# mapleSDuino-Large-V0_1_005.net
KiCad netlist of a schematic drawn in EAGLE
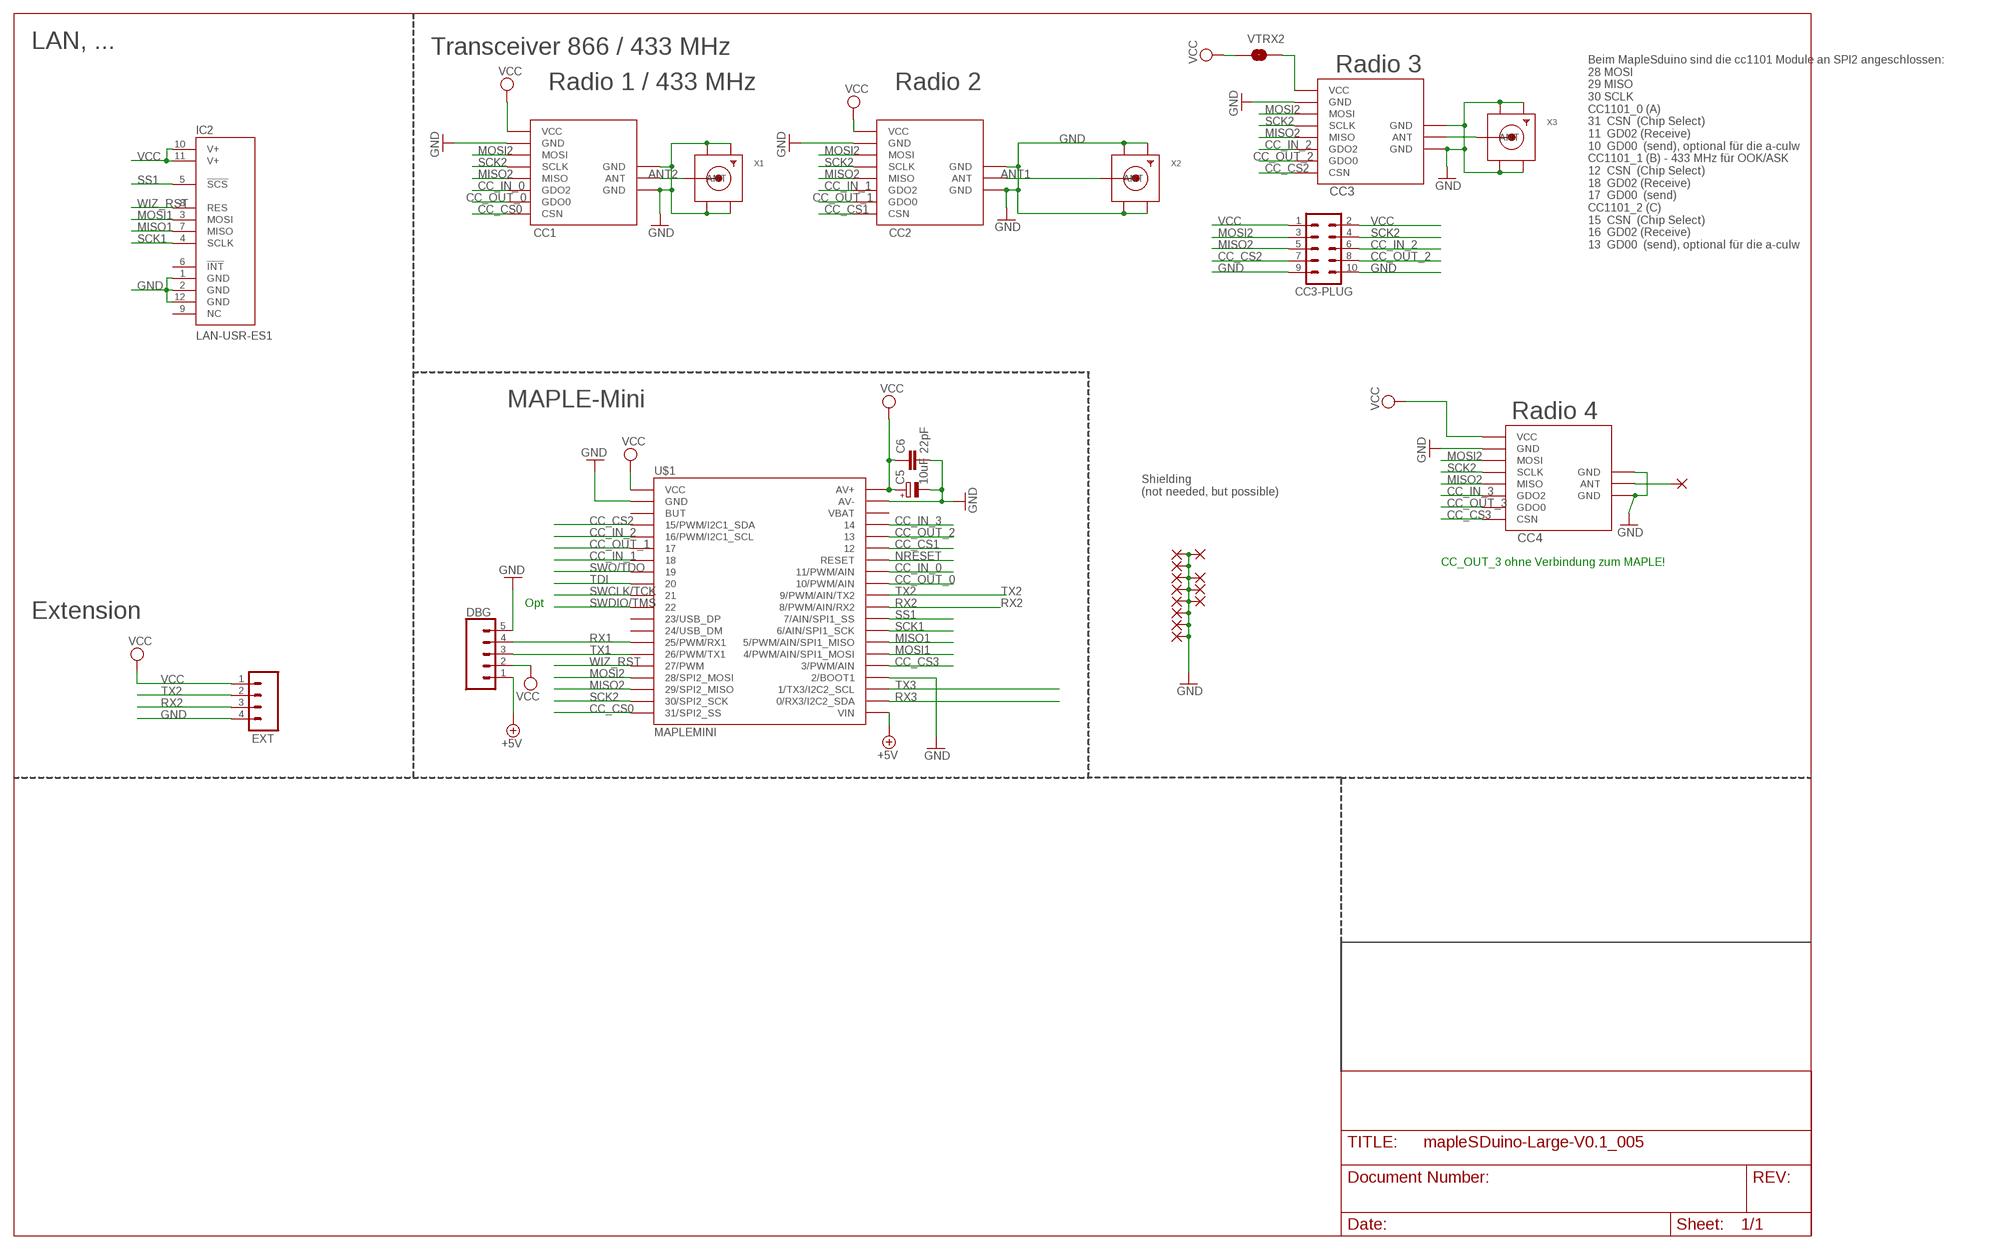
[diagram p0: schematic, sheet 1]

(export (version "E")
  (design (tool "Eeschema 10.0.6"))
  (components
    (comp (ref "C5")
      (value "10uF")
      (footprint "eagle-import:R_2012-12W")
      (libsource (lib "eagle-import") (part "CPOL-EUR/2012-12W"))
    )
    (comp (ref "C6")
      (value "22pF")
      (footprint "eagle-import:C0805")
      (libsource (lib "eagle-import") (part "C-EUC0805"))
    )
    (comp (ref "CC1")
      (value "CC1101")
      (footprint "eagle-import:CC1101_MODULE1_SMD")
      (libsource (lib "eagle-import") (part "CC1101_MODULE1SMD"))
    )
    (comp (ref "CC2")
      (value "CC1101_MODULE1SMD")
      (footprint "eagle-import:CC1101_MODULE1_SMD")
      (libsource (lib "eagle-import") (part "CC1101_MODULE1SMD"))
    )
    (comp (ref "CC3")
      (value "CC1101_MODULE1SMD")
      (footprint "eagle-import:CC1101_MODULE1_SMD")
      (libsource (lib "eagle-import") (part "wireless_CC1101_MODULE1SMD"))
    )
    (comp (ref "CC3-PLUG")
      (value "MA05-2")
      (footprint "eagle-import:MA05-2")
      (libsource (lib "eagle-import") (part "MA05-2"))
    )
    (comp (ref "CC4")
      (value "CC1101_MODULE1SMD")
      (footprint "eagle-import:CC1101_MODULE1_SMD")
      (libsource (lib "eagle-import") (part "wireless_CC1101_MODULE1SMD"))
    )
    (comp (ref "DBG")
      (value "CONN_05LOCK")
      (footprint "eagle-import:1X05_LOCK")
      (libsource (lib "eagle-import") (part "CONN_05LOCK"))
    )
    (comp (ref "EXT")
      (value "CONN_04PTH")
      (footprint "eagle-import:1X04")
      (libsource (lib "eagle-import") (part "CONN_04PTH"))
    )
    (comp (ref "IC2")
      (value "LAN-USR-ES1")
      (footprint "eagle-import:USR-ES1")
      (libsource (lib "eagle-import") (part "LAN-USR-ES1"))
    )
    (comp (ref "PAD1")
      (value "WIREPADSMD1,27-254")
      (footprint "eagle-import:SMD1,27-2,54")
      (libsource (lib "eagle-import") (part "WIREPADSMD1,27-254"))
    )
    (comp (ref "PAD2")
      (value "WIREPADSMD1,27-254")
      (footprint "eagle-import:SMD1,27-2,54")
      (libsource (lib "eagle-import") (part "WIREPADSMD1,27-254"))
    )
    (comp (ref "PAD3")
      (value "WIREPADSMD1,27-254")
      (footprint "eagle-import:SMD1,27-2,54")
      (libsource (lib "eagle-import") (part "WIREPADSMD1,27-254"))
    )
    (comp (ref "PAD4")
      (value "WIREPADSMD1,27-254")
      (footprint "eagle-import:SMD1,27-2,54")
      (libsource (lib "eagle-import") (part "WIREPADSMD1,27-254"))
    )
    (comp (ref "PAD5")
      (value "WIREPADSMD1,27-254")
      (footprint "eagle-import:SMD1,27-2,54")
      (libsource (lib "eagle-import") (part "WIREPADSMD1,27-254"))
    )
    (comp (ref "PAD6")
      (value "WIREPADSMD1,27-254")
      (footprint "eagle-import:SMD1,27-2,54")
      (libsource (lib "eagle-import") (part "WIREPADSMD1,27-254"))
    )
    (comp (ref "PAD7")
      (value "WIREPADSMD1,27-254")
      (footprint "eagle-import:SMD1,27-2,54")
      (libsource (lib "eagle-import") (part "WIREPADSMD1,27-254"))
    )
    (comp (ref "PAD8")
      (value "WIREPADSMD1,27-254")
      (footprint "eagle-import:SMD1,27-2,54")
      (libsource (lib "eagle-import") (part "WIREPADSMD1,27-254"))
    )
    (comp (ref "PAD9")
      (value "WIREPADSMD1,27-254")
      (footprint "eagle-import:SMD1,27-2,54")
      (libsource (lib "eagle-import") (part "WIREPADSMD1,27-254"))
    )
    (comp (ref "PAD10")
      (value "WIREPADSMD1,27-254")
      (footprint "eagle-import:SMD1,27-2,54")
      (libsource (lib "eagle-import") (part "WIREPADSMD1,27-254"))
    )
    (comp (ref "PAD11")
      (value "WIREPADSMD1,27-254")
      (footprint "eagle-import:SMD1,27-2,54")
      (libsource (lib "eagle-import") (part "WIREPADSMD1,27-254"))
    )
    (comp (ref "PAD12")
      (value "WIREPADSMD1,27-254")
      (footprint "eagle-import:SMD1,27-2,54")
      (libsource (lib "eagle-import") (part "WIREPADSMD1,27-254"))
    )
    (comp (ref "PAD13")
      (value "WIREPADSMD1,27-254")
      (footprint "eagle-import:SMD1,27-2,54")
      (libsource (lib "eagle-import") (part "WIREPADSMD1,27-254"))
    )
    (comp (ref "U$1")
      (value "MAPLEMINI")
      (footprint "eagle-import:20-DIP")
      (libsource (lib "eagle-import") (part "MAPLEMINI"))
    )
    (comp (ref "VTRX2")
      (value "JUMPER-SMT_2_NC_TRACE_SILK")
      (footprint "eagle-import:SMT-JUMPER_2_NC_TRACE_SILK")
      (libsource (lib "eagle-import") (part "JUMPER-SMT_2_NC_TRACE_SILK"))
    )
    (comp (ref "X1")
      (value "SMACONNECTOR_EDGE")
      (footprint "eagle-import:SMA_EDGELAUNCH")
      (libsource (lib "eagle-import") (part "SMACONNECTOR_EDGE"))
    )
    (comp (ref "X2")
      (value "SMACONNECTOR_EDGE")
      (footprint "eagle-import:SMA_EDGELAUNCH")
      (libsource (lib "eagle-import") (part "SMACONNECTOR_EDGE"))
    )
    (comp (ref "X3")
      (value "SMACONNECTOR_EDGE")
      (footprint "eagle-import:SMA_EDGELAUNCH")
      (libsource (lib "eagle-import") (part "SMACONNECTOR_EDGE"))
    )
  )
  (nets
    (net (code "1") (name "+5V") (class "Default")
      (node (ref "DBG") (pin "1") (pinfunction "1_1") (pintype "passive"))
      (node (ref "U$1") (pin "21") (pinfunction "VIN_21") (pintype "bidirectional"))
    )
    (net (code "2") (name "/ANT1") (class "Default")
      (node (ref "CC2") (pin "ANT") (pinfunction "ANT_ANT") (pintype "output"))
      (node (ref "X2") (pin "P") (pinfunction "ANT_P") (pintype "bidirectional"))
    )
    (net (code "3") (name "/ANT2") (class "Default")
      (node (ref "CC1") (pin "ANT") (pinfunction "ANT_ANT") (pintype "output"))
      (node (ref "X1") (pin "P") (pinfunction "ANT_P") (pintype "bidirectional"))
    )
    (net (code "4") (name "/CC_CS0") (class "Default")
      (node (ref "CC1") (pin "CSN") (pinfunction "CSN_CSN") (pintype "bidirectional"))
      (node (ref "U$1") (pin "20") (pinfunction "31/SPI2_SS_20") (pintype "bidirectional"))
    )
    (net (code "5") (name "/CC_CS1") (class "Default")
      (node (ref "CC2") (pin "CSN") (pinfunction "CSN_CSN") (pintype "bidirectional"))
      (node (ref "U$1") (pin "35") (pinfunction "12_35") (pintype "bidirectional"))
    )
    (net (code "6") (name "/CC_CS2") (class "Default")
      (node (ref "CC3") (pin "CSN") (pinfunction "CSN_CSN") (pintype "bidirectional"))
      (node (ref "CC3-PLUG") (pin "7") (pinfunction "7_7") (pintype "passive"))
      (node (ref "U$1") (pin "4") (pinfunction "15/PWM/I2C1_SDA_4") (pintype "bidirectional"))
    )
    (net (code "7") (name "/CC_CS3") (class "Default")
      (node (ref "CC4") (pin "CSN") (pinfunction "CSN_CSN") (pintype "bidirectional"))
      (node (ref "U$1") (pin "25") (pinfunction "3/PWM/AIN_25") (pintype "bidirectional"))
    )
    (net (code "8") (name "/CC_IN_0") (class "Default")
      (node (ref "CC1") (pin "GDO2") (pinfunction "GDO2_GDO2") (pintype "bidirectional"))
      (node (ref "U$1") (pin "33") (pinfunction "11/PWM/AIN_33") (pintype "bidirectional"))
    )
    (net (code "9") (name "/CC_IN_1") (class "Default")
      (node (ref "CC2") (pin "GDO2") (pinfunction "GDO2_GDO2") (pintype "bidirectional"))
      (node (ref "U$1") (pin "7") (pinfunction "18_7") (pintype "bidirectional"))
    )
    (net (code "10") (name "/CC_IN_2") (class "Default")
      (node (ref "CC3") (pin "GDO2") (pinfunction "GDO2_GDO2") (pintype "bidirectional"))
      (node (ref "CC3-PLUG") (pin "6") (pinfunction "6_6") (pintype "passive"))
      (node (ref "U$1") (pin "5") (pinfunction "16/PWM/I2C1_SCL_5") (pintype "bidirectional"))
    )
    (net (code "11") (name "/CC_IN_3") (class "Default")
      (node (ref "CC4") (pin "GDO2") (pinfunction "GDO2_GDO2") (pintype "bidirectional"))
      (node (ref "U$1") (pin "37") (pinfunction "14_37") (pintype "bidirectional"))
    )
    (net (code "12") (name "/CC_OUT_0") (class "Default")
      (node (ref "CC1") (pin "GDO0") (pinfunction "GDO0_GDO0") (pintype "bidirectional"))
      (node (ref "U$1") (pin "32") (pinfunction "10/PWM/AIN_32") (pintype "bidirectional"))
    )
    (net (code "13") (name "/CC_OUT_1") (class "Default")
      (node (ref "CC2") (pin "GDO0") (pinfunction "GDO0_GDO0") (pintype "bidirectional"))
      (node (ref "U$1") (pin "6") (pinfunction "17_6") (pintype "bidirectional"))
    )
    (net (code "14") (name "/CC_OUT_2") (class "Default")
      (node (ref "CC3") (pin "GDO0") (pinfunction "GDO0_GDO0") (pintype "bidirectional"))
      (node (ref "CC3-PLUG") (pin "8") (pinfunction "8_8") (pintype "passive"))
      (node (ref "U$1") (pin "36") (pinfunction "13_36") (pintype "bidirectional"))
    )
    (net (code "15") (name "/CC_OUT_3") (class "Default")
      (node (ref "CC4") (pin "GDO0") (pinfunction "GDO0_GDO0") (pintype "bidirectional"))
    )
    (net (code "16") (name "/MISO1") (class "Default")
      (node (ref "IC2") (pin "7") (pinfunction "MISO_7") (pintype "bidirectional"))
      (node (ref "U$1") (pin "27") (pinfunction "5/PWM/AIN/SPI1_MISO_27") (pintype "bidirectional"))
    )
    (net (code "17") (name "/MISO2") (class "Default")
      (node (ref "CC1") (pin "MISO") (pinfunction "MISO_MISO") (pintype "bidirectional"))
      (node (ref "CC2") (pin "MISO") (pinfunction "MISO_MISO") (pintype "bidirectional"))
      (node (ref "CC3") (pin "MISO") (pinfunction "MISO_MISO") (pintype "bidirectional"))
      (node (ref "CC3-PLUG") (pin "5") (pinfunction "5_5") (pintype "passive"))
      (node (ref "CC4") (pin "MISO") (pinfunction "MISO_MISO") (pintype "bidirectional"))
      (node (ref "U$1") (pin "18") (pinfunction "29/SPI2_MISO_18") (pintype "bidirectional"))
    )
    (net (code "18") (name "/MOSI1") (class "Default")
      (node (ref "IC2") (pin "3") (pinfunction "MOSI_3") (pintype "bidirectional"))
      (node (ref "U$1") (pin "26") (pinfunction "4/PWM/AIN/SPI1_MOSI_26") (pintype "bidirectional"))
    )
    (net (code "19") (name "/MOSI2") (class "Default")
      (node (ref "CC1") (pin "MOSI") (pinfunction "MOSI_MOSI") (pintype "bidirectional"))
      (node (ref "CC2") (pin "MOSI") (pinfunction "MOSI_MOSI") (pintype "bidirectional"))
      (node (ref "CC3") (pin "MOSI") (pinfunction "MOSI_MOSI") (pintype "bidirectional"))
      (node (ref "CC3-PLUG") (pin "3") (pinfunction "3_3") (pintype "passive"))
      (node (ref "CC4") (pin "MOSI") (pinfunction "MOSI_MOSI") (pintype "bidirectional"))
      (node (ref "U$1") (pin "17") (pinfunction "28/SPI2_MOSI_17") (pintype "bidirectional"))
    )
    (net (code "20") (name "/NRESET") (class "Default")
      (node (ref "U$1") (pin "34") (pinfunction "RESET_34") (pintype "bidirectional"))
    )
    (net (code "21") (name "/RX1") (class "Default")
      (node (ref "DBG") (pin "4") (pinfunction "4_4") (pintype "passive"))
      (node (ref "U$1") (pin "14") (pinfunction "25/PWM/RX1_14") (pintype "bidirectional"))
    )
    (net (code "22") (name "/RX2") (class "Default")
      (node (ref "EXT") (pin "3") (pinfunction "3_3") (pintype "passive"))
      (node (ref "U$1") (pin "30") (pinfunction "8/PWM/AIN/RX2_30") (pintype "bidirectional"))
    )
    (net (code "23") (name "/RX3") (class "Default")
      (node (ref "U$1") (pin "22") (pinfunction "0/RX3/I2C2_SDA_22") (pintype "bidirectional"))
    )
    (net (code "24") (name "/SCK1") (class "Default")
      (node (ref "IC2") (pin "4") (pinfunction "SCLK_4") (pintype "input"))
      (node (ref "U$1") (pin "28") (pinfunction "6/AIN/SPI1_SCK_28") (pintype "bidirectional"))
    )
    (net (code "25") (name "/SCK2") (class "Default")
      (node (ref "CC1") (pin "SCLK") (pinfunction "SCLK_SCLK") (pintype "bidirectional"))
      (node (ref "CC2") (pin "SCLK") (pinfunction "SCLK_SCLK") (pintype "bidirectional"))
      (node (ref "CC3") (pin "SCLK") (pinfunction "SCLK_SCLK") (pintype "bidirectional"))
      (node (ref "CC3-PLUG") (pin "4") (pinfunction "4_4") (pintype "passive"))
      (node (ref "CC4") (pin "SCLK") (pinfunction "SCLK_SCLK") (pintype "bidirectional"))
      (node (ref "U$1") (pin "19") (pinfunction "30/SPI2_SCK_19") (pintype "bidirectional"))
    )
    (net (code "26") (name "/SS1") (class "Default")
      (node (ref "IC2") (pin "5") (pinfunction "~{SCS}_5") (pintype "input"))
      (node (ref "U$1") (pin "29") (pinfunction "7/AIN/SPI1_SS_29") (pintype "bidirectional"))
    )
    (net (code "27") (name "/SWCLK{slash}TCK") (class "Default")
      (node (ref "U$1") (pin "10") (pinfunction "21_10") (pintype "bidirectional"))
    )
    (net (code "28") (name "/SWDIO{slash}TMS") (class "Default")
      (node (ref "U$1") (pin "11") (pinfunction "22_11") (pintype "bidirectional"))
    )
    (net (code "29") (name "/SWO{slash}TDO") (class "Default")
      (node (ref "U$1") (pin "8") (pinfunction "19_8") (pintype "bidirectional"))
    )
    (net (code "30") (name "/TDI") (class "Default")
      (node (ref "U$1") (pin "9") (pinfunction "20_9") (pintype "bidirectional"))
    )
    (net (code "31") (name "/TX1") (class "Default")
      (node (ref "DBG") (pin "3") (pinfunction "3_3") (pintype "passive"))
      (node (ref "U$1") (pin "15") (pinfunction "26/PWM/TX1_15") (pintype "bidirectional"))
    )
    (net (code "32") (name "/TX2") (class "Default")
      (node (ref "EXT") (pin "2") (pinfunction "2_2") (pintype "passive"))
      (node (ref "U$1") (pin "31") (pinfunction "9/PWM/AIN/TX2_31") (pintype "bidirectional"))
    )
    (net (code "33") (name "/TX3") (class "Default")
      (node (ref "U$1") (pin "23") (pinfunction "1/TX3/I2C2_SCL_23") (pintype "bidirectional"))
    )
    (net (code "34") (name "/WIZ_RST") (class "Default")
      (node (ref "IC2") (pin "8") (pinfunction "RES_8") (pintype "input"))
      (node (ref "U$1") (pin "16") (pinfunction "27/PWM_16") (pintype "bidirectional"))
    )
    (net (code "35") (name "GND") (class "Default")
      (node (ref "C5") (pin "-") (pinfunction "-_-") (pintype "passive"))
      (node (ref "C6") (pin "2") (pinfunction "2_2") (pintype "passive"))
      (node (ref "CC1") (pin "GND@0") (pinfunction "GND_GND@0") (pintype "power_in"))
      (node (ref "CC1") (pin "GND@1") (pinfunction "GND_GND@1") (pintype "power_in"))
      (node (ref "CC1") (pin "GND@2") (pinfunction "GND_GND@2") (pintype "power_in"))
      (node (ref "CC2") (pin "GND@0") (pinfunction "GND_GND@0") (pintype "power_in"))
      (node (ref "CC2") (pin "GND@1") (pinfunction "GND_GND@1") (pintype "power_in"))
      (node (ref "CC2") (pin "GND@2") (pinfunction "GND_GND@2") (pintype "power_in"))
      (node (ref "CC3") (pin "GND@0") (pinfunction "GND_GND@0") (pintype "power_in"))
      (node (ref "CC3") (pin "GND@1") (pinfunction "GND_GND@1") (pintype "power_in"))
      (node (ref "CC3") (pin "GND@2") (pinfunction "GND_GND@2") (pintype "power_in"))
      (node (ref "CC3-PLUG") (pin "10") (pinfunction "10_10") (pintype "passive"))
      (node (ref "CC3-PLUG") (pin "9") (pinfunction "9_9") (pintype "passive"))
      (node (ref "CC4") (pin "GND@0") (pinfunction "GND_GND@0") (pintype "power_in"))
      (node (ref "CC4") (pin "GND@1") (pinfunction "GND_GND@1") (pintype "power_in"))
      (node (ref "CC4") (pin "GND@2") (pinfunction "GND_GND@2") (pintype "power_in"))
      (node (ref "DBG") (pin "5") (pinfunction "5_5") (pintype "passive"))
      (node (ref "EXT") (pin "4") (pinfunction "4_4") (pintype "passive"))
      (node (ref "IC2") (pin "1") (pinfunction "GND_1") (pintype "power_in"))
      (node (ref "IC2") (pin "12") (pinfunction "GND_12") (pintype "power_in"))
      (node (ref "IC2") (pin "2") (pinfunction "GND_2") (pintype "power_in"))
      (node (ref "PAD1") (pin "1") (pinfunction "P_1") (pintype "passive"))
      (node (ref "PAD10") (pin "1") (pinfunction "P_1") (pintype "passive"))
      (node (ref "PAD11") (pin "1") (pinfunction "P_1") (pintype "passive"))
      (node (ref "PAD12") (pin "1") (pinfunction "P_1") (pintype "passive"))
      (node (ref "PAD2") (pin "1") (pinfunction "P_1") (pintype "passive"))
      (node (ref "PAD3") (pin "1") (pinfunction "P_1") (pintype "passive"))
      (node (ref "PAD4") (pin "1") (pinfunction "P_1") (pintype "passive"))
      (node (ref "PAD5") (pin "1") (pinfunction "P_1") (pintype "passive"))
      (node (ref "PAD6") (pin "1") (pinfunction "P_1") (pintype "passive"))
      (node (ref "PAD7") (pin "1") (pinfunction "P_1") (pintype "passive"))
      (node (ref "PAD8") (pin "1") (pinfunction "P_1") (pintype "passive"))
      (node (ref "PAD9") (pin "1") (pinfunction "P_1") (pintype "passive"))
      (node (ref "U$1") (pin "2") (pinfunction "GND_2") (pintype "bidirectional"))
      (node (ref "U$1") (pin "24") (pinfunction "2/BOOT1_24") (pintype "bidirectional"))
      (node (ref "U$1") (pin "39") (pinfunction "AV-_39") (pintype "bidirectional"))
      (node (ref "X1") (pin "GND@1") (pinfunction "GND4_GND@1") (pintype "power_in"))
      (node (ref "X1") (pin "GND@2") (pinfunction "GND3_GND@2") (pintype "power_in"))
      (node (ref "X1") (pin "GND@3") (pinfunction "GND2_GND@3") (pintype "power_in"))
      (node (ref "X1") (pin "GND@4") (pinfunction "GND1_GND@4") (pintype "power_in"))
      (node (ref "X2") (pin "GND@1") (pinfunction "GND4_GND@1") (pintype "power_in"))
      (node (ref "X2") (pin "GND@2") (pinfunction "GND3_GND@2") (pintype "power_in"))
      (node (ref "X2") (pin "GND@3") (pinfunction "GND2_GND@3") (pintype "power_in"))
      (node (ref "X2") (pin "GND@4") (pinfunction "GND1_GND@4") (pintype "power_in"))
      (node (ref "X3") (pin "GND@1") (pinfunction "GND4_GND@1") (pintype "power_in"))
      (node (ref "X3") (pin "GND@2") (pinfunction "GND3_GND@2") (pintype "power_in"))
      (node (ref "X3") (pin "GND@3") (pinfunction "GND2_GND@3") (pintype "power_in"))
      (node (ref "X3") (pin "GND@4") (pinfunction "GND1_GND@4") (pintype "power_in"))
    )
    (net (code "36") (name "Net-(CC3-PadVCC)") (class "Default")
      (node (ref "CC3") (pin "VCC") (pinfunction "VCC_VCC") (pintype "power_in"))
      (node (ref "VTRX2") (pin "2") (pinfunction "2_2") (pintype "passive"))
    )
    (net (code "37") (name "Net-(PAD13-P)") (class "Default")
      (node (ref "CC4") (pin "ANT") (pinfunction "ANT_ANT") (pintype "output"))
      (node (ref "PAD13") (pin "1") (pinfunction "P_1") (pintype "passive"))
    )
    (net (code "38") (name "Net-(X3-ANT)") (class "Default")
      (node (ref "CC3") (pin "ANT") (pinfunction "ANT_ANT") (pintype "output"))
      (node (ref "X3") (pin "P") (pinfunction "ANT_P") (pintype "bidirectional"))
    )
    (net (code "39") (name "VCC") (class "Default")
      (node (ref "C5") (pin "+") (pinfunction "+_+") (pintype "passive"))
      (node (ref "C6") (pin "1") (pinfunction "1_1") (pintype "passive"))
      (node (ref "CC1") (pin "VCC") (pinfunction "VCC_VCC") (pintype "power_in"))
      (node (ref "CC2") (pin "VCC") (pinfunction "VCC_VCC") (pintype "power_in"))
      (node (ref "CC3-PLUG") (pin "1") (pinfunction "1_1") (pintype "passive"))
      (node (ref "CC3-PLUG") (pin "2") (pinfunction "2_2") (pintype "passive"))
      (node (ref "CC4") (pin "VCC") (pinfunction "VCC_VCC") (pintype "power_in"))
      (node (ref "DBG") (pin "2") (pinfunction "2_2") (pintype "passive"))
      (node (ref "EXT") (pin "1") (pinfunction "1_1") (pintype "passive"))
      (node (ref "IC2") (pin "10") (pinfunction "V+_10") (pintype "power_in"))
      (node (ref "IC2") (pin "11") (pinfunction "V+_11") (pintype "power_in"))
      (node (ref "U$1") (pin "1") (pinfunction "VCC_1") (pintype "bidirectional"))
      (node (ref "U$1") (pin "40") (pinfunction "AV+_40") (pintype "bidirectional"))
      (node (ref "VTRX2") (pin "1") (pinfunction "1_1") (pintype "passive"))
    )
    (net (code "40") (name "unconnected-(IC2-NC-Pad9)") (class "Default")
      (node (ref "IC2") (pin "9") (pinfunction "NC_9") (pintype "no_connect"))
    )
    (net (code "41") (name "unconnected-(IC2-~{INT}-Pad6)") (class "Default")
      (node (ref "IC2") (pin "6") (pinfunction "~{INT}_6") (pintype "output"))
    )
    (net (code "42") (name "unconnected-(U$1-23{slash}USB_DP-Pad12)") (class "Default")
      (node (ref "U$1") (pin "12") (pinfunction "23/USB_DP_12") (pintype "bidirectional"))
    )
    (net (code "43") (name "unconnected-(U$1-24{slash}USB_DM-Pad13)") (class "Default")
      (node (ref "U$1") (pin "13") (pinfunction "24/USB_DM_13") (pintype "bidirectional"))
    )
    (net (code "44") (name "unconnected-(U$1-BUT-Pad3)") (class "Default")
      (node (ref "U$1") (pin "3") (pinfunction "BUT_3") (pintype "bidirectional"))
    )
    (net (code "45") (name "unconnected-(U$1-VBAT-Pad38)") (class "Default")
      (node (ref "U$1") (pin "38") (pinfunction "VBAT_38") (pintype "bidirectional"))
    )
  )
)
